# Esquematico.net
KiCad netlist of a schematic drawn in EAGLE
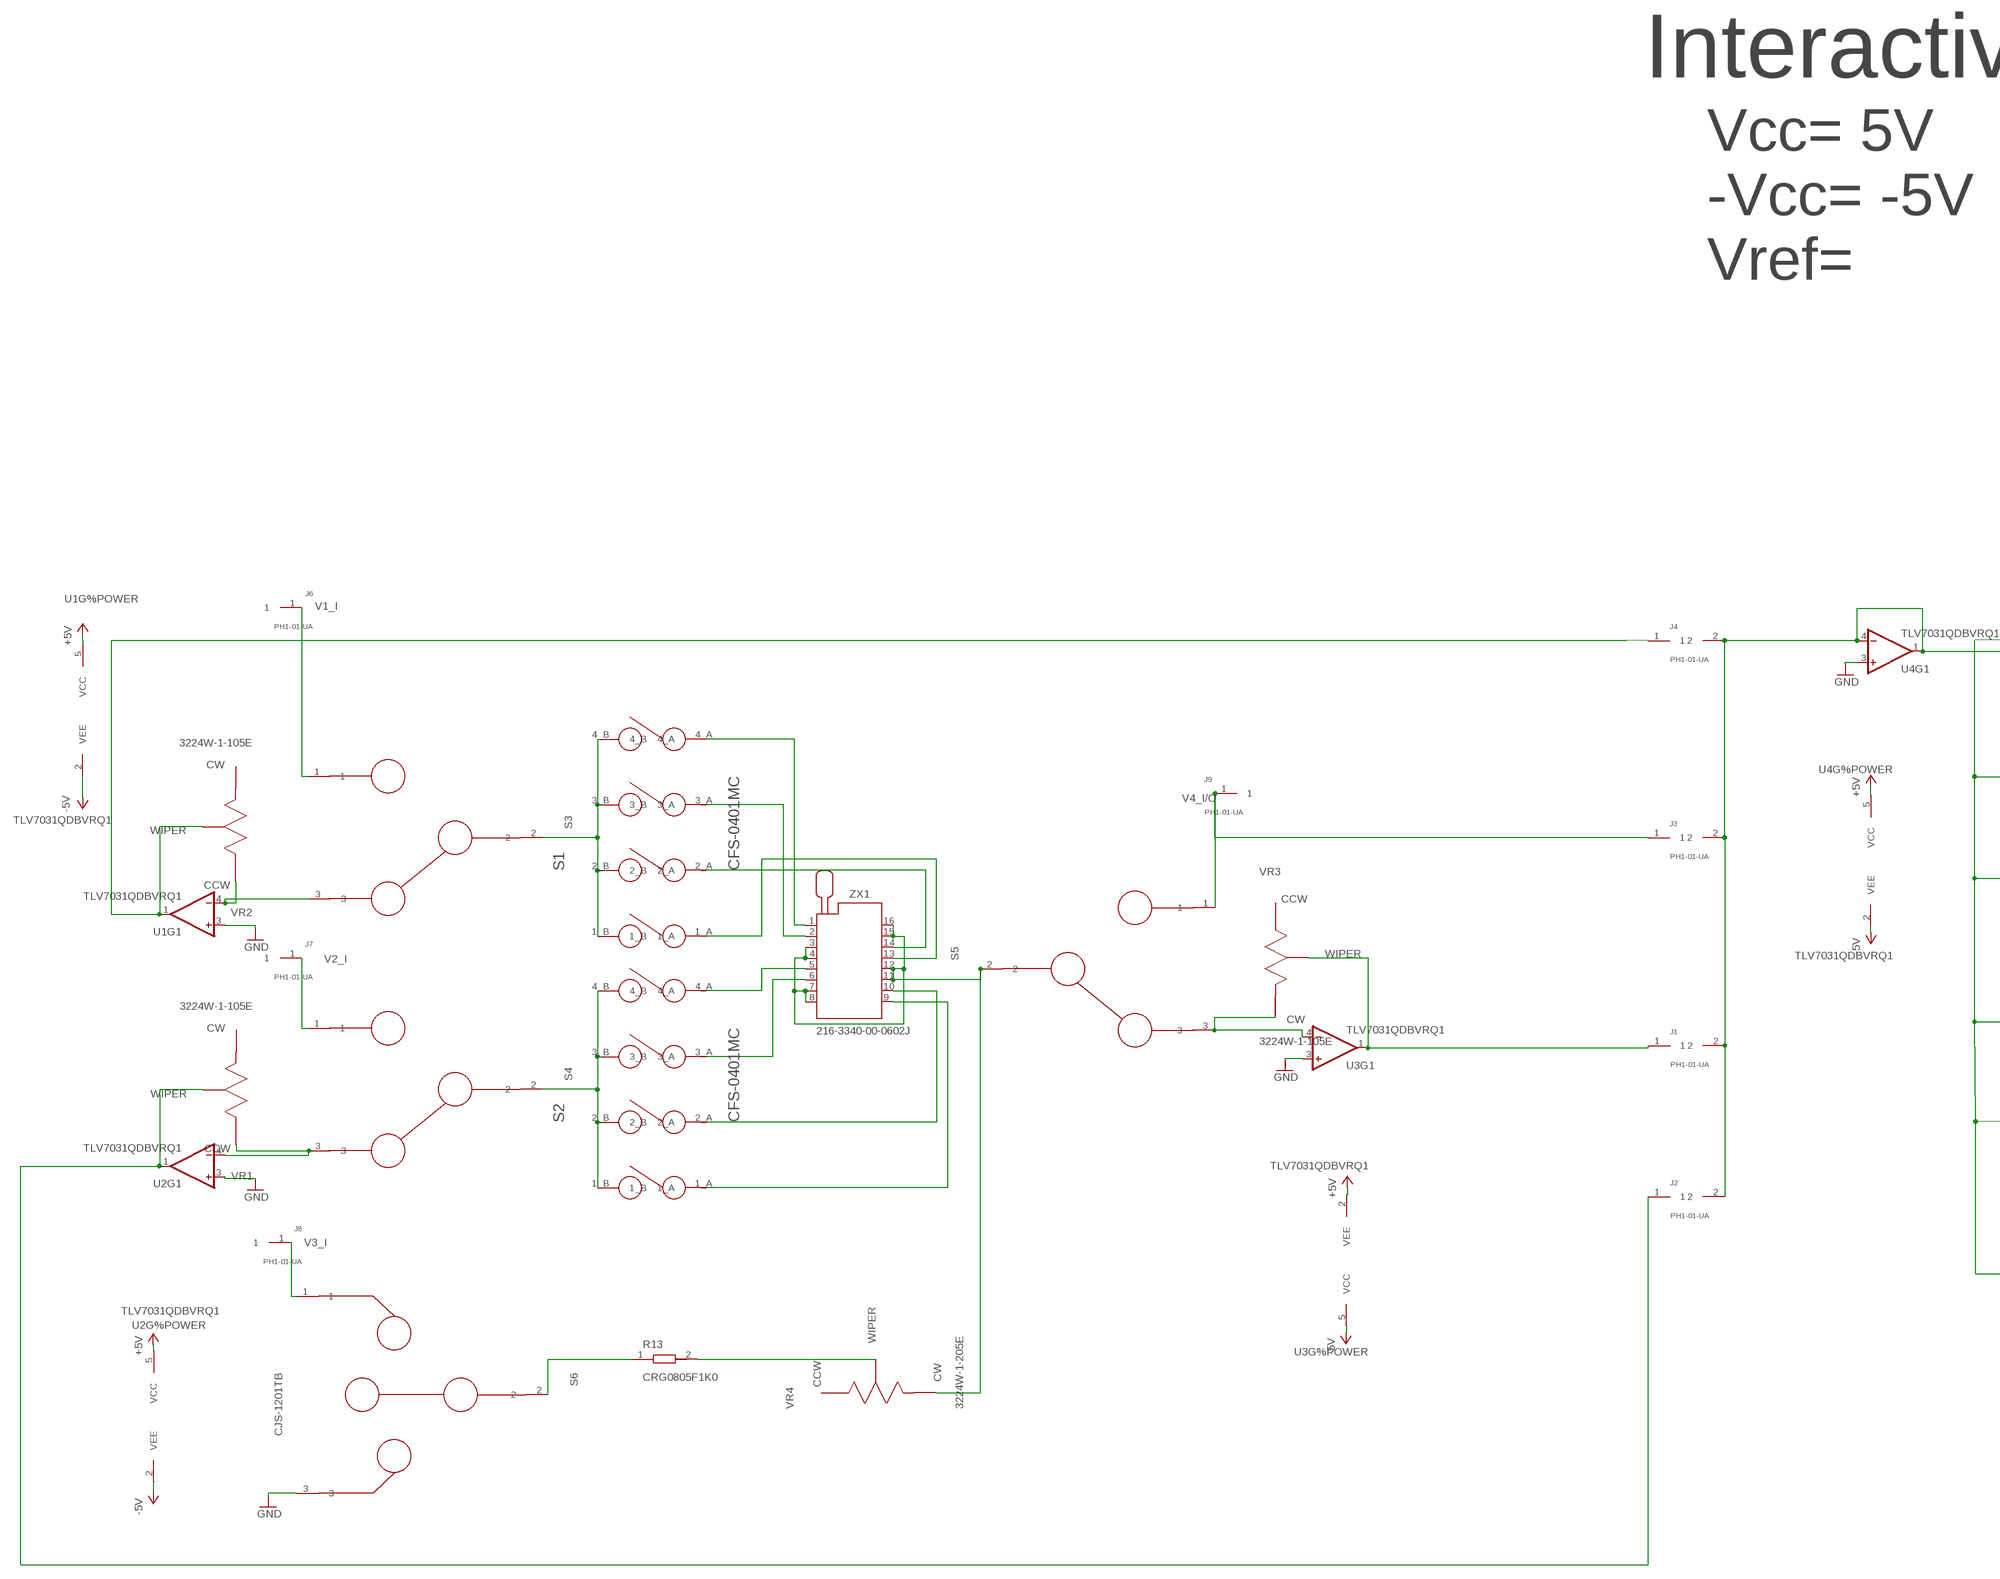
[diagram p0: schematic, sheet 1, part 1 of 2]
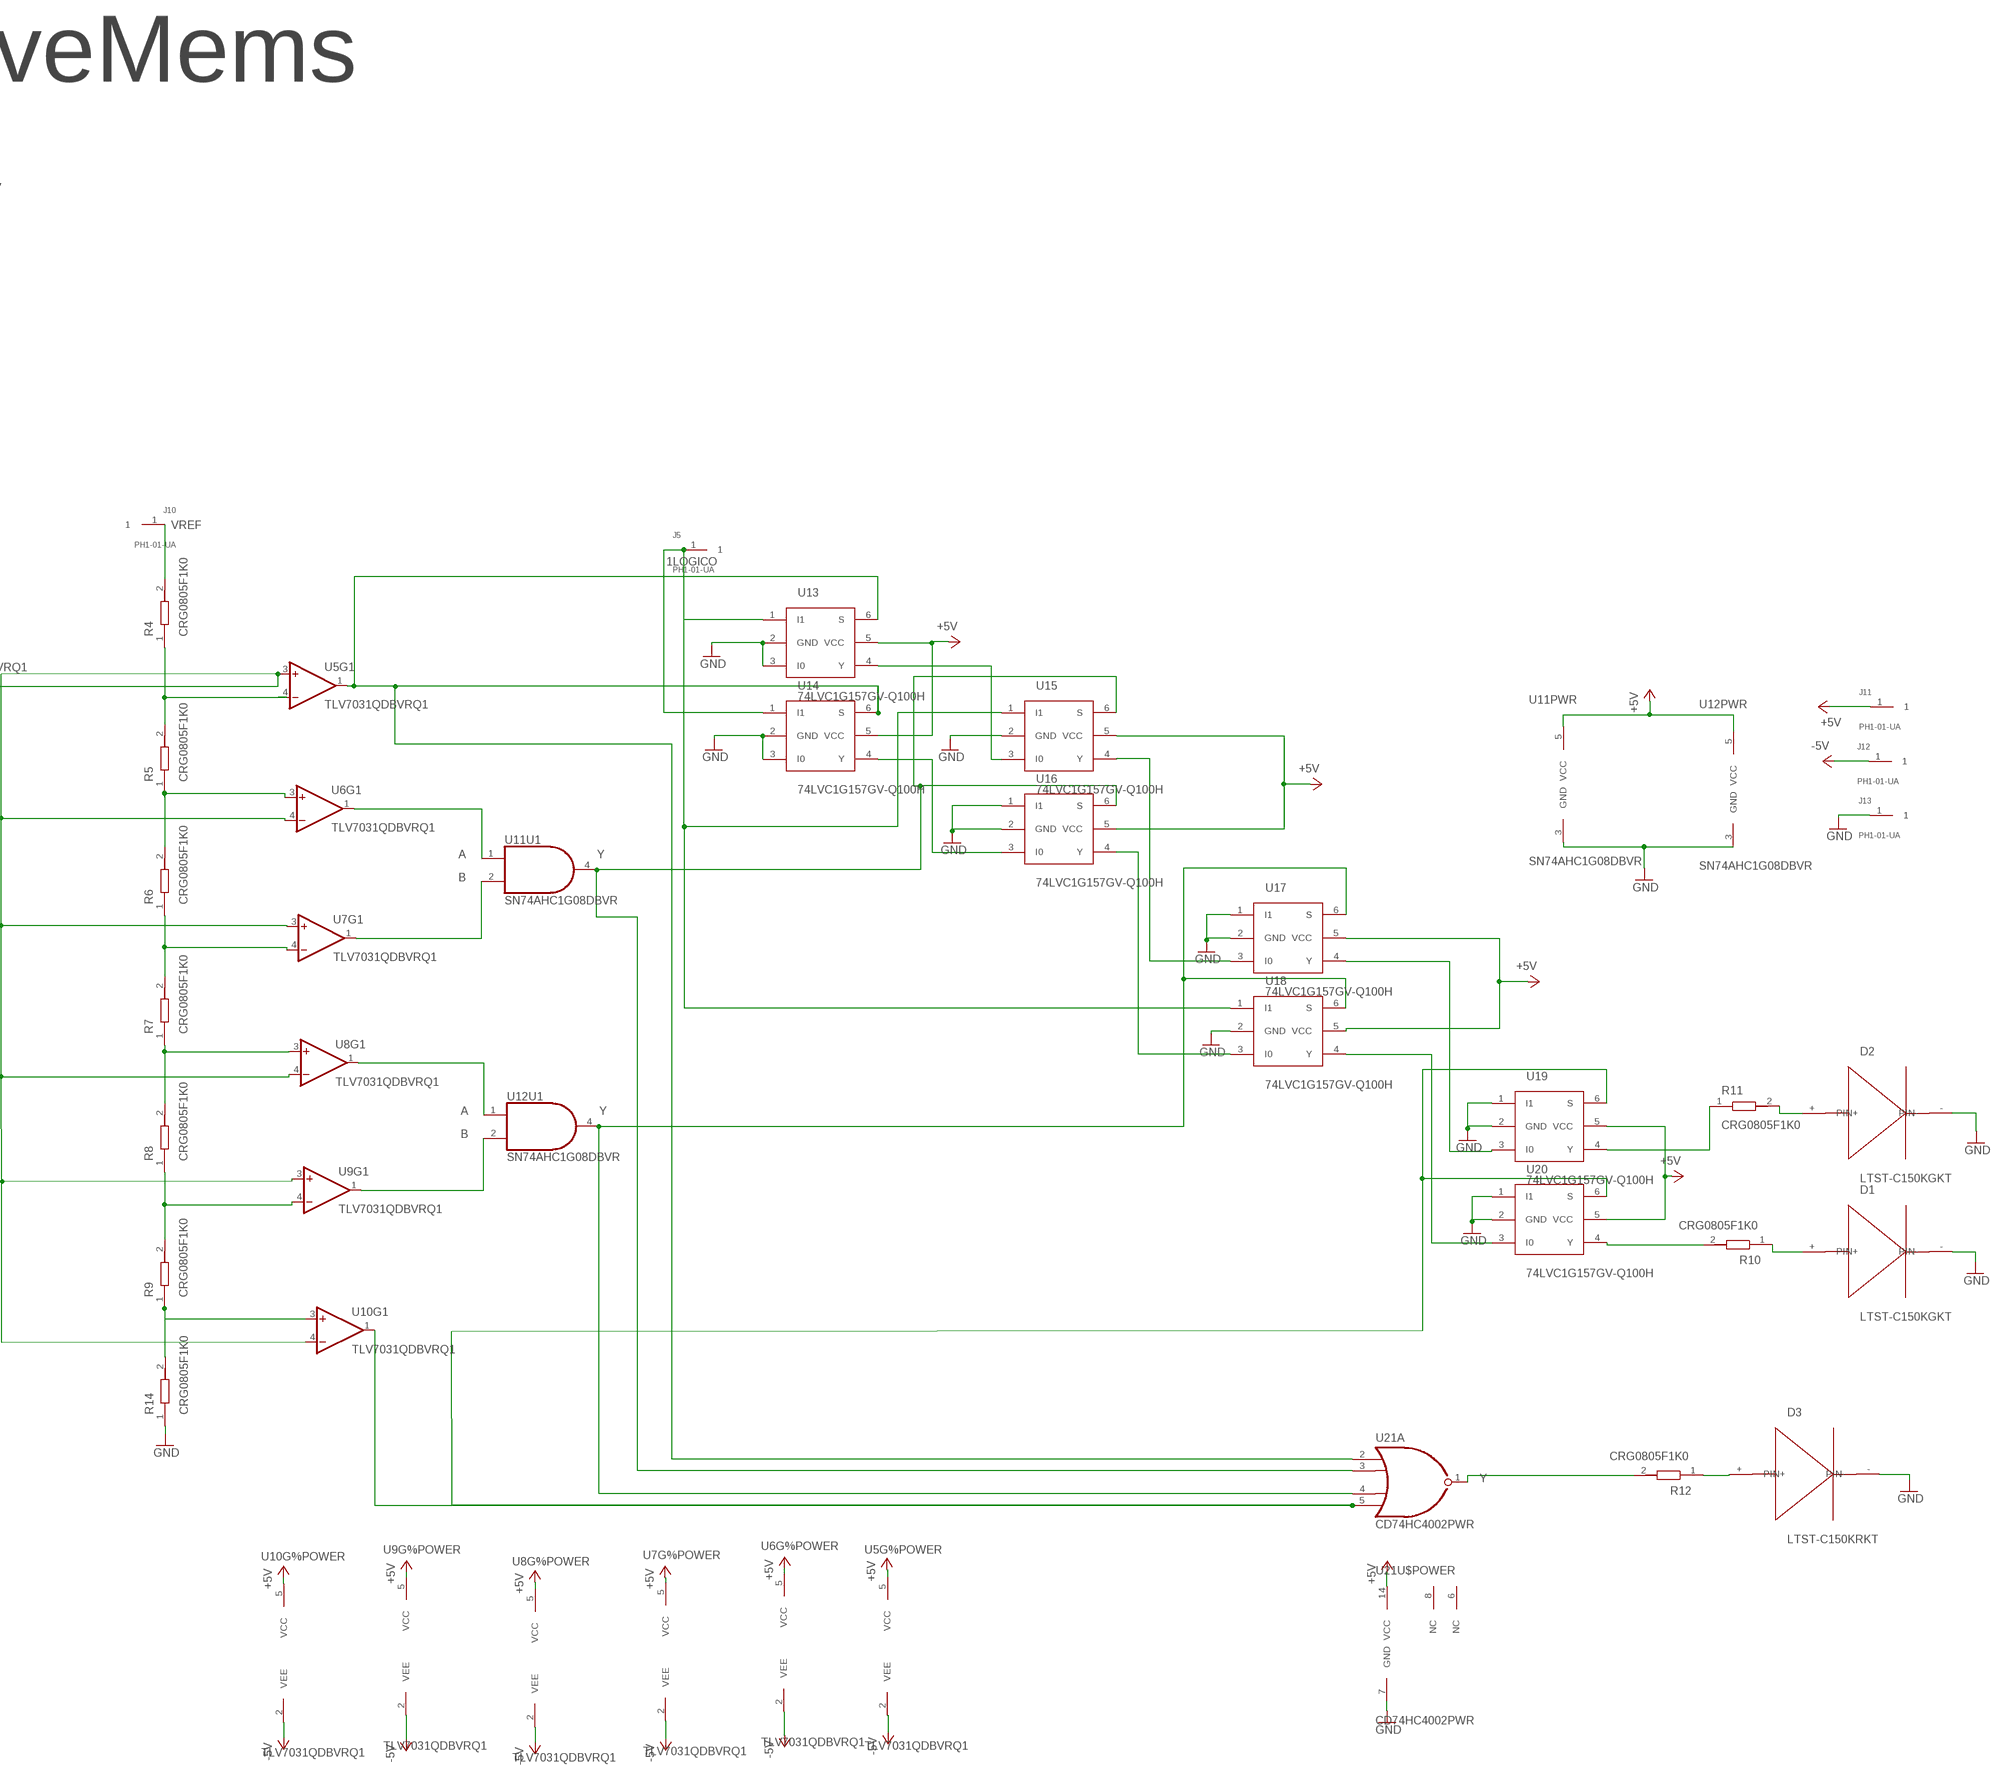
[diagram p1: schematic, sheet 1, part 2 of 2]

(export (version "E")
  (design (tool "Eeschema 10.0.6"))
  (components
    (comp (ref "D1")
      (value "LTST-C150KGKT")
      (footprint "eagle-import:1206")
      (libsource (lib "eagle-import") (part "LTST-C150KRKT"))
    )
    (comp (ref "D2")
      (value "LTST-C150KGKT")
      (footprint "eagle-import:1206")
      (libsource (lib "eagle-import") (part "LTST-C150KRKT"))
    )
    (comp (ref "D3")
      (value "LTST-C150KRKT")
      (footprint "eagle-import:1206")
      (libsource (lib "eagle-import") (part "LTST-C150KRKT"))
    )
    (comp (ref "J1")
      (value "PH1-01-UA")
      (footprint "eagle-import:HEADER")
      (libsource (lib "eagle-import") (part "(2X)PH1-01-UA"))
    )
    (comp (ref "J2")
      (value "PH1-01-UA")
      (footprint "eagle-import:HEADER")
      (libsource (lib "eagle-import") (part "(2X)PH1-01-UA"))
    )
    (comp (ref "J3")
      (value "PH1-01-UA")
      (footprint "eagle-import:HEADER")
      (libsource (lib "eagle-import") (part "(2X)PH1-01-UA"))
    )
    (comp (ref "J4")
      (value "PH1-01-UA")
      (footprint "eagle-import:HEADER")
      (libsource (lib "eagle-import") (part "(2X)PH1-01-UA"))
    )
    (comp (ref "J5")
      (value "PH1-01-UA")
      (footprint "eagle-import:HEADER")
      (libsource (lib "eagle-import") (part "PH1-01-UA"))
    )
    (comp (ref "J6")
      (value "PH1-01-UA")
      (footprint "eagle-import:HEADER")
      (libsource (lib "eagle-import") (part "PH1-01-UA"))
    )
    (comp (ref "J7")
      (value "PH1-01-UA")
      (footprint "eagle-import:HEADER")
      (libsource (lib "eagle-import") (part "PH1-01-UA"))
    )
    (comp (ref "J8")
      (value "PH1-01-UA")
      (footprint "eagle-import:HEADER")
      (libsource (lib "eagle-import") (part "PH1-01-UA"))
    )
    (comp (ref "J9")
      (value "PH1-01-UA")
      (footprint "eagle-import:HEADER")
      (libsource (lib "eagle-import") (part "PH1-01-UA"))
    )
    (comp (ref "J10")
      (value "PH1-01-UA")
      (footprint "eagle-import:HEADER")
      (libsource (lib "eagle-import") (part "PH1-01-UA"))
    )
    (comp (ref "J11")
      (value "PH1-01-UA")
      (footprint "eagle-import:HEADER")
      (fields (field (name "PARTNO") "PH1-01-UA "))
      (libsource (lib "eagle-import") (part "PH1-01-UA"))
    )
    (comp (ref "J12")
      (value "PH1-01-UA")
      (footprint "eagle-import:HEADER")
      (fields (field (name "PARTNO") "PH1-01-UA "))
      (libsource (lib "eagle-import") (part "PH1-01-UA"))
    )
    (comp (ref "J13")
      (value "PH1-01-UA")
      (footprint "eagle-import:HEADER")
      (fields (field (name "PARTNO") "PH1-01-UA "))
      (libsource (lib "eagle-import") (part "PH1-01-UA"))
    )
    (comp (ref "R4")
      (value "CRG0805F1K0")
      (footprint "eagle-import:0805")
      (fields (field (name "PARTNO") "CRG0805F1K0 "))
      (libsource (lib "eagle-import") (part "CRG0805F1K0"))
    )
    (comp (ref "R5")
      (value "CRG0805F1K0")
      (footprint "eagle-import:0805")
      (fields (field (name "PARTNO") "CRG0805F1K0 "))
      (libsource (lib "eagle-import") (part "CRG0805F1K0"))
    )
    (comp (ref "R6")
      (value "CRG0805F1K0")
      (footprint "eagle-import:0805")
      (fields (field (name "PARTNO") "CRG0805F1K0 "))
      (libsource (lib "eagle-import") (part "CRG0805F1K0"))
    )
    (comp (ref "R7")
      (value "CRG0805F1K0")
      (footprint "eagle-import:0805")
      (fields (field (name "PARTNO") "CRG0805F1K0 "))
      (libsource (lib "eagle-import") (part "CRG0805F1K0"))
    )
    (comp (ref "R8")
      (value "CRG0805F1K0")
      (footprint "eagle-import:0805")
      (fields (field (name "PARTNO") "CRG0805F1K0 "))
      (libsource (lib "eagle-import") (part "CRG0805F1K0"))
    )
    (comp (ref "R9")
      (value "CRG0805F1K0")
      (footprint "eagle-import:0805")
      (fields (field (name "PARTNO") "CRG0805F1K0 "))
      (libsource (lib "eagle-import") (part "CRG0805F1K0"))
    )
    (comp (ref "R10")
      (value "CRG0805F1K0")
      (footprint "eagle-import:0805")
      (fields (field (name "PARTNO") "CRG0805F1K0 "))
      (libsource (lib "eagle-import") (part "CRG0805F1K0"))
    )
    (comp (ref "R11")
      (value "CRG0805F1K0")
      (footprint "eagle-import:0805")
      (fields (field (name "PARTNO") "CRG0805F1K0 "))
      (libsource (lib "eagle-import") (part "CRG0805F1K0"))
    )
    (comp (ref "R12")
      (value "CRG0805F1K0")
      (footprint "eagle-import:0805")
      (fields (field (name "PARTNO") "CRG0805F1K0 "))
      (libsource (lib "eagle-import") (part "CRG0805F1K0"))
    )
    (comp (ref "R13")
      (value "CRG0805F1K0")
      (footprint "eagle-import:0805")
      (libsource (lib "eagle-import") (part "CRG0805F1K0"))
    )
    (comp (ref "R14")
      (value "CRG0805F1K0")
      (footprint "eagle-import:0805")
      (fields (field (name "PARTNO") "CRG0805F1K0 "))
      (libsource (lib "eagle-import") (part "CRG0805F1K0"))
    )
    (comp (ref "S1")
      (value "CFS-0401MC")
      (footprint "eagle-import:DIP_SPST-4")
      (libsource (lib "eagle-import") (part "CFS-0401MC"))
    )
    (comp (ref "S2")
      (value "CFS-0401MC")
      (footprint "eagle-import:DIP_SPST-4")
      (libsource (lib "eagle-import") (part "CFS-0401MC"))
    )
    (comp (ref "S3")
      (value "CJS-1200TB")
      (footprint "eagle-import:SPDT")
      (libsource (lib "eagle-import") (part "CJS-1200B"))
    )
    (comp (ref "S4")
      (value "CJS-1200TB")
      (footprint "eagle-import:SPDT")
      (libsource (lib "eagle-import") (part "CJS-1200B"))
    )
    (comp (ref "S5")
      (value "CJS-1200TB")
      (footprint "eagle-import:SPDT")
      (libsource (lib "eagle-import") (part "CJS-1200B"))
    )
    (comp (ref "S6")
      (value "CJS-1201TB")
      (footprint "eagle-import:SPDT_ON-OFF-ON")
      (libsource (lib "eagle-import") (part "CJS-1201TB"))
    )
    (comp (ref "U1")
      (value "TLV7031QDBVRQ1")
      (footprint "eagle-import:SOT-23")
      (fields (field (name "PARTNO") "TLV7031QDBVRQ1"))
      (libsource (lib "eagle-import") (part "TLV7031QDBVRQ1"))
    )
    (comp (ref "U2")
      (value "TLV7031QDBVRQ1")
      (footprint "eagle-import:SOT-23")
      (fields (field (name "PARTNO") "TLV7031QDBVRQ1"))
      (libsource (lib "eagle-import") (part "TLV7031QDBVRQ1"))
    )
    (comp (ref "U3")
      (value "TLV7031QDBVRQ1")
      (footprint "eagle-import:SOT-23")
      (fields (field (name "PARTNO") "TLV7031QDBVRQ1"))
      (libsource (lib "eagle-import") (part "TLV7031QDBVRQ1"))
    )
    (comp (ref "U4")
      (value "TLV7031QDBVRQ1")
      (footprint "eagle-import:SOT-23")
      (fields (field (name "PARTNO") "TLV7031QDBVRQ1"))
      (libsource (lib "eagle-import") (part "TLV7031QDBVRQ1"))
    )
    (comp (ref "U5")
      (value "TLV7031QDBVRQ1")
      (footprint "eagle-import:SOT-23")
      (fields (field (name "PARTNO") "TLV7031QDBVRQ1"))
      (libsource (lib "eagle-import") (part "TLV7031QDBVRQ1"))
    )
    (comp (ref "U6")
      (value "TLV7031QDBVRQ1")
      (footprint "eagle-import:SOT-23")
      (fields (field (name "PARTNO") "TLV7031QDBVRQ1"))
      (libsource (lib "eagle-import") (part "TLV7031QDBVRQ1"))
    )
    (comp (ref "U7")
      (value "TLV7031QDBVRQ1")
      (footprint "eagle-import:SOT-23")
      (fields (field (name "PARTNO") "TLV7031QDBVRQ1"))
      (libsource (lib "eagle-import") (part "TLV7031QDBVRQ1"))
    )
    (comp (ref "U8")
      (value "TLV7031QDBVRQ1")
      (footprint "eagle-import:SOT-23")
      (fields (field (name "PARTNO") "TLV7031QDBVRQ1"))
      (libsource (lib "eagle-import") (part "TLV7031QDBVRQ1"))
    )
    (comp (ref "U9")
      (value "TLV7031QDBVRQ1")
      (footprint "eagle-import:SOT-23")
      (fields (field (name "PARTNO") "TLV7031QDBVRQ1"))
      (libsource (lib "eagle-import") (part "TLV7031QDBVRQ1"))
    )
    (comp (ref "U10")
      (value "TLV7031QDBVRQ1")
      (footprint "eagle-import:SOT-23")
      (fields (field (name "PARTNO") "TLV7031QDBVRQ1"))
      (libsource (lib "eagle-import") (part "TLV7031QDBVRQ1"))
    )
    (comp (ref "U11")
      (value "SN74AHC1G08DBVR")
      (footprint "eagle-import:SOT-23-5")
      (fields (field (name "PARTNO") "SN74AHC1G08DBVR"))
      (libsource (lib "eagle-import") (part "SN74AHC1G08DBVR"))
    )
    (comp (ref "U12")
      (value "SN74AHC1G08DBVR")
      (footprint "eagle-import:SOT-23-5")
      (fields (field (name "PARTNO") "SN74AHC1G08DBVR"))
      (libsource (lib "eagle-import") (part "SN74AHC1G08DBVR"))
    )
    (comp (ref "U13")
      (value "74LVC1G157GV-Q100H")
      (footprint "eagle-import:6-TSOP")
      (libsource (lib "eagle-import") (part "74LVC1G157GV-Q100H"))
    )
    (comp (ref "U14")
      (value "74LVC1G157GV-Q100H")
      (footprint "eagle-import:6-TSOP")
      (libsource (lib "eagle-import") (part "74LVC1G157GV-Q100H"))
    )
    (comp (ref "U15")
      (value "74LVC1G157GV-Q100H")
      (footprint "eagle-import:6-TSOP")
      (libsource (lib "eagle-import") (part "74LVC1G157GV-Q100H"))
    )
    (comp (ref "U16")
      (value "74LVC1G157GV-Q100H")
      (footprint "eagle-import:6-TSOP")
      (libsource (lib "eagle-import") (part "74LVC1G157GV-Q100H"))
    )
    (comp (ref "U17")
      (value "74LVC1G157GV-Q100H")
      (footprint "eagle-import:6-TSOP")
      (libsource (lib "eagle-import") (part "74LVC1G157GV-Q100H"))
    )
    (comp (ref "U18")
      (value "74LVC1G157GV-Q100H")
      (footprint "eagle-import:6-TSOP")
      (libsource (lib "eagle-import") (part "74LVC1G157GV-Q100H"))
    )
    (comp (ref "U19")
      (value "74LVC1G157GV-Q100H")
      (footprint "eagle-import:6-TSOP")
      (libsource (lib "eagle-import") (part "74LVC1G157GV-Q100H"))
    )
    (comp (ref "U20")
      (value "74LVC1G157GV-Q100H")
      (footprint "eagle-import:6-TSOP")
      (libsource (lib "eagle-import") (part "74LVC1G157GV-Q100H"))
    )
    (comp (ref "U21")
      (value "CD74HC4002PWR")
      (footprint "eagle-import:14-TSSOP")
      (fields (field (name "PARTNO") "CD74HC4002PWR"))
      (libsource (lib "eagle-import") (part "CD74HC4002PWR"))
    )
    (comp (ref "VR1")
      (value "3224W-1-105E")
      (footprint "eagle-import:3224W-1-205E")
      (libsource (lib "eagle-import") (part "3224W-1-205E"))
    )
    (comp (ref "VR2")
      (value "3224W-1-105E")
      (footprint "eagle-import:3224W-1-205E")
      (libsource (lib "eagle-import") (part "3224W-1-205E"))
    )
    (comp (ref "VR3")
      (value "3224W-1-105E")
      (footprint "eagle-import:3224W-1-205E")
      (libsource (lib "eagle-import") (part "3224W-1-205E"))
    )
    (comp (ref "VR4")
      (value "3224W-1-205E")
      (footprint "eagle-import:3224W-1-205E")
      (libsource (lib "eagle-import") (part "3224W-1-205E"))
    )
    (comp (ref "ZX1")
      (value "216-3340-00-0602J")
      (footprint "eagle-import:216-3340-00-0602J")
      (libsource (lib "eagle-import") (part "216-3340-00-0602J"))
    )
  )
  (nets
    (net (code "1") (name "+5V") (class "Default")
      (node (ref "J11") (pin "1") (pinfunction "1_1") (pintype "passive"))
      (node (ref "U1") (pin "5") (pinfunction "VCC_5") (pintype "power_in"))
      (node (ref "U10") (pin "5") (pinfunction "VCC_5") (pintype "power_in"))
      (node (ref "U11") (pin "5") (pinfunction "VCC_5") (pintype "power_in"))
      (node (ref "U12") (pin "5") (pinfunction "VCC_5") (pintype "power_in"))
      (node (ref "U13") (pin "5") (pinfunction "VCC_5") (pintype "power_in"))
      (node (ref "U14") (pin "5") (pinfunction "VCC_5") (pintype "power_in"))
      (node (ref "U15") (pin "5") (pinfunction "VCC_5") (pintype "power_in"))
      (node (ref "U16") (pin "5") (pinfunction "VCC_5") (pintype "power_in"))
      (node (ref "U17") (pin "5") (pinfunction "VCC_5") (pintype "power_in"))
      (node (ref "U18") (pin "5") (pinfunction "VCC_5") (pintype "power_in"))
      (node (ref "U19") (pin "5") (pinfunction "VCC_5") (pintype "power_in"))
      (node (ref "U2") (pin "5") (pinfunction "VCC_5") (pintype "power_in"))
      (node (ref "U20") (pin "5") (pinfunction "VCC_5") (pintype "power_in"))
      (node (ref "U21") (pin "14") (pinfunction "VCC_14") (pintype "power_in"))
      (node (ref "U3") (pin "2") (pinfunction "VEE_2") (pintype "power_in"))
      (node (ref "U4") (pin "5") (pinfunction "VCC_5") (pintype "power_in"))
      (node (ref "U5") (pin "5") (pinfunction "VCC_5") (pintype "power_in"))
      (node (ref "U6") (pin "5") (pinfunction "VCC_5") (pintype "power_in"))
      (node (ref "U7") (pin "5") (pinfunction "VCC_5") (pintype "power_in"))
      (node (ref "U8") (pin "5") (pinfunction "VCC_5") (pintype "power_in"))
      (node (ref "U9") (pin "5") (pinfunction "VCC_5") (pintype "power_in"))
    )
    (net (code "2") (name "-5V") (class "Default")
      (node (ref "J12") (pin "1") (pinfunction "1_1") (pintype "passive"))
      (node (ref "U1") (pin "2") (pinfunction "VEE_2") (pintype "power_in"))
      (node (ref "U10") (pin "2") (pinfunction "VEE_2") (pintype "power_in"))
      (node (ref "U2") (pin "2") (pinfunction "VEE_2") (pintype "power_in"))
      (node (ref "U3") (pin "5") (pinfunction "VCC_5") (pintype "power_in"))
      (node (ref "U4") (pin "2") (pinfunction "VEE_2") (pintype "power_in"))
      (node (ref "U5") (pin "2") (pinfunction "VEE_2") (pintype "power_in"))
      (node (ref "U6") (pin "2") (pinfunction "VEE_2") (pintype "power_in"))
      (node (ref "U7") (pin "2") (pinfunction "VEE_2") (pintype "power_in"))
      (node (ref "U8") (pin "2") (pinfunction "VEE_2") (pintype "power_in"))
      (node (ref "U9") (pin "2") (pinfunction "VEE_2") (pintype "power_in"))
    )
    (net (code "3") (name "/1LOGICO") (class "Default")
      (node (ref "J5") (pin "1") (pinfunction "1_1") (pintype "passive"))
      (node (ref "U13") (pin "1") (pinfunction "I1_1") (pintype "input"))
      (node (ref "U14") (pin "1") (pinfunction "I1_1") (pintype "input"))
      (node (ref "U15") (pin "1") (pinfunction "I1_1") (pintype "input"))
      (node (ref "U18") (pin "1") (pinfunction "I1_1") (pintype "input"))
    )
    (net (code "4") (name "/V1_I") (class "Default")
      (node (ref "J6") (pin "1") (pinfunction "1_1") (pintype "passive"))
      (node (ref "S3") (pin "1") (pinfunction "1_1") (pintype "passive"))
    )
    (net (code "5") (name "/V2_I") (class "Default")
      (node (ref "J7") (pin "1") (pinfunction "1_1") (pintype "passive"))
      (node (ref "S4") (pin "1") (pinfunction "1_1") (pintype "passive"))
    )
    (net (code "6") (name "/V3_I") (class "Default")
      (node (ref "J8") (pin "1") (pinfunction "1_1") (pintype "passive"))
      (node (ref "S6") (pin "1") (pinfunction "1_1") (pintype "passive"))
    )
    (net (code "7") (name "/V4_I{slash}O") (class "Default")
      (node (ref "J3") (pin "1") (pinfunction "1_1") (pintype "passive"))
      (node (ref "J9") (pin "1") (pinfunction "1_1") (pintype "passive"))
      (node (ref "S5") (pin "1") (pinfunction "1_1") (pintype "passive"))
    )
    (net (code "8") (name "/VREF") (class "Default")
      (node (ref "J10") (pin "1") (pinfunction "1_1") (pintype "passive"))
      (node (ref "R4") (pin "2") (pinfunction "P$2_2") (pintype "passive"))
    )
    (net (code "9") (name "GND") (class "Default")
      (node (ref "D1") (pin "-") (pinfunction "PIN-_-") (pintype "passive"))
      (node (ref "D2") (pin "-") (pinfunction "PIN-_-") (pintype "passive"))
      (node (ref "D3") (pin "-") (pinfunction "PIN-_-") (pintype "passive"))
      (node (ref "J13") (pin "1") (pinfunction "1_1") (pintype "passive"))
      (node (ref "R14") (pin "1") (pinfunction "P$1_1") (pintype "passive"))
      (node (ref "S6") (pin "3") (pinfunction "3_3") (pintype "passive"))
      (node (ref "U1") (pin "3") (pinfunction "+IN_3") (pintype "input"))
      (node (ref "U11") (pin "3") (pinfunction "GND_3") (pintype "power_in"))
      (node (ref "U12") (pin "3") (pinfunction "GND_3") (pintype "power_in"))
      (node (ref "U13") (pin "2") (pinfunction "GND_2") (pintype "power_in"))
      (node (ref "U13") (pin "3") (pinfunction "I0_3") (pintype "input"))
      (node (ref "U14") (pin "2") (pinfunction "GND_2") (pintype "power_in"))
      (node (ref "U14") (pin "3") (pinfunction "I0_3") (pintype "input"))
      (node (ref "U15") (pin "2") (pinfunction "GND_2") (pintype "power_in"))
      (node (ref "U16") (pin "1") (pinfunction "I1_1") (pintype "input"))
      (node (ref "U16") (pin "2") (pinfunction "GND_2") (pintype "power_in"))
      (node (ref "U17") (pin "1") (pinfunction "I1_1") (pintype "input"))
      (node (ref "U17") (pin "2") (pinfunction "GND_2") (pintype "power_in"))
      (node (ref "U18") (pin "2") (pinfunction "GND_2") (pintype "power_in"))
      (node (ref "U19") (pin "1") (pinfunction "I1_1") (pintype "input"))
      (node (ref "U19") (pin "2") (pinfunction "GND_2") (pintype "power_in"))
      (node (ref "U2") (pin "3") (pinfunction "+IN_3") (pintype "input"))
      (node (ref "U20") (pin "1") (pinfunction "I1_1") (pintype "input"))
      (node (ref "U20") (pin "2") (pinfunction "GND_2") (pintype "power_in"))
      (node (ref "U21") (pin "7") (pinfunction "GND_7") (pintype "power_in"))
      (node (ref "U3") (pin "3") (pinfunction "+IN_3") (pintype "input"))
      (node (ref "U4") (pin "3") (pinfunction "+IN_3") (pintype "input"))
    )
    (net (code "10") (name "Net-(D1-PIN+)") (class "Default")
      (node (ref "D1") (pin "+") (pinfunction "PIN+_+") (pintype "passive"))
      (node (ref "R10") (pin "1") (pinfunction "P$1_1") (pintype "passive"))
    )
    (net (code "11") (name "Net-(D2-PIN+)") (class "Default")
      (node (ref "D2") (pin "+") (pinfunction "PIN+_+") (pintype "passive"))
      (node (ref "R11") (pin "2") (pinfunction "P$2_2") (pintype "passive"))
    )
    (net (code "12") (name "Net-(D3-PIN+)") (class "Default")
      (node (ref "D3") (pin "+") (pinfunction "PIN+_+") (pintype "passive"))
      (node (ref "R12") (pin "1") (pinfunction "P$1_1") (pintype "passive"))
    )
    (net (code "13") (name "Net-(R4-P$1)") (class "Default")
      (node (ref "R4") (pin "1") (pinfunction "P$1_1") (pintype "passive"))
      (node (ref "R5") (pin "2") (pinfunction "P$2_2") (pintype "passive"))
      (node (ref "U5") (pin "4") (pinfunction "-IN_4") (pintype "input"))
    )
    (net (code "14") (name "Net-(R5-P$1)") (class "Default")
      (node (ref "R5") (pin "1") (pinfunction "P$1_1") (pintype "passive"))
      (node (ref "R6") (pin "2") (pinfunction "P$2_2") (pintype "passive"))
      (node (ref "U6") (pin "3") (pinfunction "+IN_3") (pintype "input"))
    )
    (net (code "15") (name "Net-(R6-P$1)") (class "Default")
      (node (ref "R6") (pin "1") (pinfunction "P$1_1") (pintype "passive"))
      (node (ref "R7") (pin "2") (pinfunction "P$2_2") (pintype "passive"))
      (node (ref "U7") (pin "4") (pinfunction "-IN_4") (pintype "input"))
    )
    (net (code "16") (name "Net-(R7-P$1)") (class "Default")
      (node (ref "R7") (pin "1") (pinfunction "P$1_1") (pintype "passive"))
      (node (ref "R8") (pin "2") (pinfunction "P$2_2") (pintype "passive"))
      (node (ref "U8") (pin "3") (pinfunction "+IN_3") (pintype "input"))
    )
    (net (code "17") (name "Net-(R8-P$1)") (class "Default")
      (node (ref "R8") (pin "1") (pinfunction "P$1_1") (pintype "passive"))
      (node (ref "R9") (pin "2") (pinfunction "P$2_2") (pintype "passive"))
      (node (ref "U9") (pin "4") (pinfunction "-IN_4") (pintype "input"))
    )
    (net (code "18") (name "Net-(R10-P$2)") (class "Default")
      (node (ref "R10") (pin "2") (pinfunction "P$2_2") (pintype "passive"))
      (node (ref "U20") (pin "4") (pinfunction "Y_4") (pintype "output"))
    )
    (net (code "19") (name "Net-(R11-P$1)") (class "Default")
      (node (ref "R11") (pin "1") (pinfunction "P$1_1") (pintype "passive"))
      (node (ref "U19") (pin "4") (pinfunction "Y_4") (pintype "output"))
    )
    (net (code "20") (name "Net-(R12-P$2)") (class "Default")
      (node (ref "R12") (pin "2") (pinfunction "P$2_2") (pintype "passive"))
      (node (ref "U21") (pin "1") (pinfunction "Y_1") (pintype "output"))
    )
    (net (code "21") (name "Net-(R13-P$1)") (class "Default")
      (node (ref "R13") (pin "1") (pinfunction "P$1_1") (pintype "passive"))
      (node (ref "S6") (pin "2") (pinfunction "2_2") (pintype "passive"))
    )
    (net (code "22") (name "Net-(R13-P$2)") (class "Default")
      (node (ref "R13") (pin "2") (pinfunction "P$2_2") (pintype "passive"))
      (node (ref "VR4") (pin "2") (pinfunction "WIPER_2") (pintype "passive"))
    )
    (net (code "23") (name "Net-(R14-P$2)") (class "Default")
      (node (ref "R14") (pin "2") (pinfunction "P$2_2") (pintype "passive"))
      (node (ref "R9") (pin "1") (pinfunction "P$1_1") (pintype "passive"))
      (node (ref "U10") (pin "3") (pinfunction "+IN_3") (pintype "input"))
    )
    (net (code "24") (name "Net-(S1-Pad1_A)") (class "Default")
      (node (ref "S1") (pin "1_A") (pinfunction "1_A_1_A") (pintype "passive"))
      (node (ref "ZX1") (pin "13") (pinfunction "13_13") (pintype "passive"))
    )
    (net (code "25") (name "Net-(S1-Pad1_B)") (class "Default")
      (node (ref "S1") (pin "1_B") (pinfunction "1_B_1_B") (pintype "passive"))
      (node (ref "S1") (pin "2_B") (pinfunction "2_B_2_B") (pintype "passive"))
      (node (ref "S1") (pin "3_B") (pinfunction "3_B_3_B") (pintype "passive"))
      (node (ref "S1") (pin "4_B") (pinfunction "4_B_4_B") (pintype "passive"))
      (node (ref "S3") (pin "2") (pinfunction "2_2") (pintype "passive"))
    )
    (net (code "26") (name "Net-(S1-Pad2_A)") (class "Default")
      (node (ref "S1") (pin "2_A") (pinfunction "2_A_2_A") (pintype "passive"))
      (node (ref "ZX1") (pin "14") (pinfunction "14_14") (pintype "passive"))
    )
    (net (code "27") (name "Net-(S1-Pad3_A)") (class "Default")
      (node (ref "S1") (pin "3_A") (pinfunction "3_A_3_A") (pintype "passive"))
      (node (ref "ZX1") (pin "2") (pinfunction "2_2") (pintype "passive"))
    )
    (net (code "28") (name "Net-(S1-Pad4_A)") (class "Default")
      (node (ref "S1") (pin "4_A") (pinfunction "4_A_4_A") (pintype "passive"))
      (node (ref "ZX1") (pin "1") (pinfunction "1_1") (pintype "passive"))
    )
    (net (code "29") (name "Net-(S2-Pad1_A)") (class "Default")
      (node (ref "S2") (pin "1_A") (pinfunction "1_A_1_A") (pintype "passive"))
      (node (ref "ZX1") (pin "9") (pinfunction "9_9") (pintype "passive"))
    )
    (net (code "30") (name "Net-(S2-Pad1_B)") (class "Default")
      (node (ref "S2") (pin "1_B") (pinfunction "1_B_1_B") (pintype "passive"))
      (node (ref "S2") (pin "2_B") (pinfunction "2_B_2_B") (pintype "passive"))
      (node (ref "S2") (pin "3_B") (pinfunction "3_B_3_B") (pintype "passive"))
      (node (ref "S2") (pin "4_B") (pinfunction "4_B_4_B") (pintype "passive"))
      (node (ref "S4") (pin "2") (pinfunction "2_2") (pintype "passive"))
    )
    (net (code "31") (name "Net-(S2-Pad2_A)") (class "Default")
      (node (ref "S2") (pin "2_A") (pinfunction "2_A_2_A") (pintype "passive"))
      (node (ref "ZX1") (pin "10") (pinfunction "10_10") (pintype "passive"))
    )
    (net (code "32") (name "Net-(S2-Pad3_A)") (class "Default")
      (node (ref "S2") (pin "3_A") (pinfunction "3_A_3_A") (pintype "passive"))
      (node (ref "ZX1") (pin "6") (pinfunction "6_6") (pintype "passive"))
    )
    (net (code "33") (name "Net-(S2-Pad4_A)") (class "Default")
      (node (ref "S2") (pin "4_A") (pinfunction "4_A_4_A") (pintype "passive"))
      (node (ref "ZX1") (pin "5") (pinfunction "5_5") (pintype "passive"))
    )
    (net (code "34") (name "Net-(U1B--IN)") (class "Default")
      (node (ref "S3") (pin "3") (pinfunction "3_3") (pintype "passive"))
      (node (ref "U1") (pin "4") (pinfunction "-IN_4") (pintype "input"))
      (node (ref "VR2") (pin "1") (pinfunction "CCW_1") (pintype "passive"))
    )
    (net (code "35") (name "Net-(U1B-OUT)") (class "Default")
      (node (ref "J4") (pin "1") (pinfunction "1_1") (pintype "passive"))
      (node (ref "U1") (pin "1") (pinfunction "OUT_1") (pintype "output"))
      (node (ref "VR2") (pin "2") (pinfunction "WIPER_2") (pintype "passive"))
    )
    (net (code "36") (name "Net-(U2B--IN)") (class "Default")
      (node (ref "S4") (pin "3") (pinfunction "3_3") (pintype "passive"))
      (node (ref "U2") (pin "4") (pinfunction "-IN_4") (pintype "input"))
      (node (ref "VR1") (pin "1") (pinfunction "CCW_1") (pintype "passive"))
    )
    (net (code "37") (name "Net-(U2B-OUT)") (class "Default")
      (node (ref "J2") (pin "1") (pinfunction "1_1") (pintype "passive"))
      (node (ref "U2") (pin "1") (pinfunction "OUT_1") (pintype "output"))
      (node (ref "VR1") (pin "2") (pinfunction "WIPER_2") (pintype "passive"))
    )
    (net (code "38") (name "Net-(U3B--IN)") (class "Default")
      (node (ref "S5") (pin "3") (pinfunction "3_3") (pintype "passive"))
      (node (ref "U3") (pin "4") (pinfunction "-IN_4") (pintype "input"))
      (node (ref "VR3") (pin "3") (pinfunction "CW_3") (pintype "passive"))
    )
    (net (code "39") (name "Net-(U3B-OUT)") (class "Default")
      (node (ref "J1") (pin "1") (pinfunction "1_1") (pintype "passive"))
      (node (ref "U3") (pin "1") (pinfunction "OUT_1") (pintype "output"))
      (node (ref "VR3") (pin "2") (pinfunction "WIPER_2") (pintype "passive"))
    )
    (net (code "40") (name "Net-(U10B--IN)") (class "Default")
      (node (ref "J1") (pin "2") (pinfunction "2_2") (pintype "passive"))
      (node (ref "J2") (pin "2") (pinfunction "2_2") (pintype "passive"))
      (node (ref "J3") (pin "2") (pinfunction "2_2") (pintype "passive"))
      (node (ref "J4") (pin "2") (pinfunction "2_2") (pintype "passive"))
      (node (ref "U10") (pin "4") (pinfunction "-IN_4") (pintype "input"))
      (node (ref "U4") (pin "1") (pinfunction "OUT_1") (pintype "output"))
      (node (ref "U4") (pin "4") (pinfunction "-IN_4") (pintype "input"))
      (node (ref "U5") (pin "3") (pinfunction "+IN_3") (pintype "input"))
      (node (ref "U6") (pin "4") (pinfunction "-IN_4") (pintype "input"))
      (node (ref "U7") (pin "3") (pinfunction "+IN_3") (pintype "input"))
      (node (ref "U8") (pin "4") (pinfunction "-IN_4") (pintype "input"))
      (node (ref "U9") (pin "3") (pinfunction "+IN_3") (pintype "input"))
    )
    (net (code "41") (name "Net-(U10B-OUT)") (class "Default")
      (node (ref "U10") (pin "1") (pinfunction "OUT_1") (pintype "output"))
      (node (ref "U19") (pin "6") (pinfunction "S_6") (pintype "input"))
      (node (ref "U20") (pin "6") (pinfunction "S_6") (pintype "input"))
      (node (ref "U21") (pin "5") (pinfunction "D_5") (pintype "input"))
    )
    (net (code "42") (name "Net-(U11B-A)") (class "Default")
      (node (ref "U11") (pin "1") (pinfunction "A_1") (pintype "input"))
      (node (ref "U6") (pin "1") (pinfunction "OUT_1") (pintype "output"))
    )
    (net (code "43") (name "Net-(U11B-B)") (class "Default")
      (node (ref "U11") (pin "2") (pinfunction "B_2") (pintype "input"))
      (node (ref "U7") (pin "1") (pinfunction "OUT_1") (pintype "output"))
    )
    (net (code "44") (name "Net-(U11B-Y)") (class "Default")
      (node (ref "U11") (pin "4") (pinfunction "Y_4") (pintype "output"))
      (node (ref "U15") (pin "6") (pinfunction "S_6") (pintype "input"))
      (node (ref "U16") (pin "6") (pinfunction "S_6") (pintype "input"))
      (node (ref "U21") (pin "3") (pinfunction "B_3") (pintype "input"))
    )
    (net (code "45") (name "Net-(U12B-A)") (class "Default")
      (node (ref "U12") (pin "1") (pinfunction "A_1") (pintype "input"))
      (node (ref "U8") (pin "1") (pinfunction "OUT_1") (pintype "output"))
    )
    (net (code "46") (name "Net-(U12B-B)") (class "Default")
      (node (ref "U12") (pin "2") (pinfunction "B_2") (pintype "input"))
      (node (ref "U9") (pin "1") (pinfunction "OUT_1") (pintype "output"))
    )
    (net (code "47") (name "Net-(U12B-Y)") (class "Default")
      (node (ref "U12") (pin "4") (pinfunction "Y_4") (pintype "output"))
      (node (ref "U17") (pin "6") (pinfunction "S_6") (pintype "input"))
      (node (ref "U18") (pin "6") (pinfunction "S_6") (pintype "input"))
      (node (ref "U21") (pin "4") (pinfunction "C_4") (pintype "input"))
    )
    (net (code "48") (name "Net-(U13-S)") (class "Default")
      (node (ref "U13") (pin "6") (pinfunction "S_6") (pintype "input"))
      (node (ref "U14") (pin "6") (pinfunction "S_6") (pintype "input"))
      (node (ref "U21") (pin "2") (pinfunction "A_2") (pintype "input"))
      (node (ref "U5") (pin "1") (pinfunction "OUT_1") (pintype "output"))
    )
    (net (code "49") (name "Net-(U13-Y)") (class "Default")
      (node (ref "U13") (pin "4") (pinfunction "Y_4") (pintype "output"))
      (node (ref "U15") (pin "3") (pinfunction "I0_3") (pintype "input"))
    )
    (net (code "50") (name "Net-(U14-Y)") (class "Default")
      (node (ref "U14") (pin "4") (pinfunction "Y_4") (pintype "output"))
      (node (ref "U16") (pin "3") (pinfunction "I0_3") (pintype "input"))
    )
    (net (code "51") (name "Net-(U15-Y)") (class "Default")
      (node (ref "U15") (pin "4") (pinfunction "Y_4") (pintype "output"))
      (node (ref "U17") (pin "3") (pinfunction "I0_3") (pintype "input"))
    )
    (net (code "52") (name "Net-(U16-Y)") (class "Default")
      (node (ref "U16") (pin "4") (pinfunction "Y_4") (pintype "output"))
      (node (ref "U18") (pin "3") (pinfunction "I0_3") (pintype "input"))
    )
    (net (code "53") (name "Net-(U17-Y)") (class "Default")
      (node (ref "U17") (pin "4") (pinfunction "Y_4") (pintype "output"))
      (node (ref "U19") (pin "3") (pinfunction "I0_3") (pintype "input"))
    )
    (net (code "54") (name "Net-(U18-Y)") (class "Default")
      (node (ref "U18") (pin "4") (pinfunction "Y_4") (pintype "output"))
      (node (ref "U20") (pin "3") (pinfunction "I0_3") (pintype "input"))
    )
    (net (code "55") (name "Net-(VR4-CW)") (class "Default")
      (node (ref "S5") (pin "2") (pinfunction "2_2") (pintype "passive"))
      (node (ref "VR4") (pin "3") (pinfunction "CW_3") (pintype "passive"))
      (node (ref "ZX1") (pin "11") (pinfunction "11_11") (pintype "passive"))
      (node (ref "ZX1") (pin "12") (pinfunction "12_12") (pintype "passive"))
      (node (ref "ZX1") (pin "15") (pinfunction "15_15") (pintype "passive"))
      (node (ref "ZX1") (pin "16") (pinfunction "16_16") (pintype "passive"))
      (node (ref "ZX1") (pin "3") (pinfunction "3_3") (pintype "passive"))
      (node (ref "ZX1") (pin "4") (pinfunction "4_4") (pintype "passive"))
      (node (ref "ZX1") (pin "7") (pinfunction "7_7") (pintype "passive"))
      (node (ref "ZX1") (pin "8") (pinfunction "8_8") (pintype "passive"))
    )
    (net (code "56") (name "unconnected-(U21C-NC-Pad6)") (class "Default")
      (node (ref "U21") (pin "6") (pinfunction "NC_6") (pintype "no_connect"))
    )
    (net (code "57") (name "unconnected-(U21C-NC-Pad8)") (class "Default")
      (node (ref "U21") (pin "8") (pinfunction "NC_8") (pintype "no_connect"))
    )
    (net (code "58") (name "unconnected-(VR1-CW-Pad3)") (class "Default")
      (node (ref "VR1") (pin "3") (pinfunction "CW_3") (pintype "passive"))
    )
    (net (code "59") (name "unconnected-(VR2-CW-Pad3)") (class "Default")
      (node (ref "VR2") (pin "3") (pinfunction "CW_3") (pintype "passive"))
    )
    (net (code "60") (name "unconnected-(VR3-CCW-Pad1)") (class "Default")
      (node (ref "VR3") (pin "1") (pinfunction "CCW_1") (pintype "passive"))
    )
    (net (code "61") (name "unconnected-(VR4-CCW-Pad1)") (class "Default")
      (node (ref "VR4") (pin "1") (pinfunction "CCW_1") (pintype "passive"))
    )
  )
)
